# HEX1.net
KiCad netlist of a schematic drawn in Altium Designer
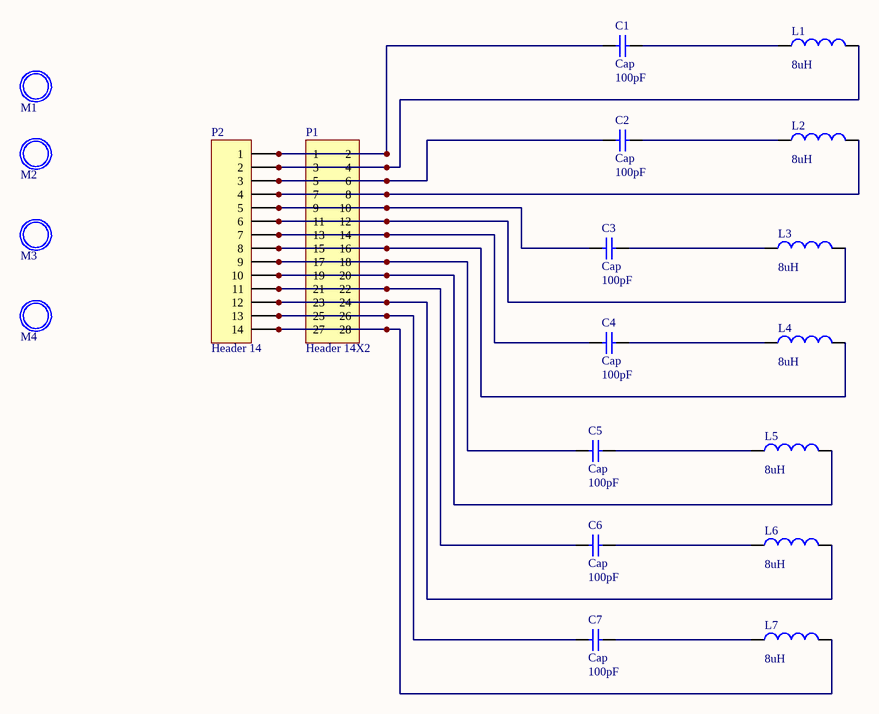
[diagram p0: HEX1.SchDoc]

(export (version "E")
  (design (tool "Eeschema 10.0.6"))
  (components
    (comp (ref "C1")
      (value "Cap")
      (footprint "CAP_MKT")
      (description "Capacitor")
      (fields (field (name "ALTIUM_VALUE") "100pF") (field (name "PUBLISHER") "Altium Limited"))
      (libsource (lib "Miscellaneous Devices") (part "Cap"))
    )
    (comp (ref "C2")
      (value "Cap")
      (footprint "CAP_MKT")
      (description "Capacitor")
      (fields (field (name "ALTIUM_VALUE") "100pF") (field (name "PUBLISHER") "Altium Limited"))
      (libsource (lib "Miscellaneous Devices") (part "Cap"))
    )
    (comp (ref "C3")
      (value "Cap")
      (footprint "CAP_MKT")
      (description "Capacitor")
      (fields (field (name "ALTIUM_VALUE") "100pF") (field (name "PUBLISHER") "Altium Limited"))
      (libsource (lib "Miscellaneous Devices") (part "Cap"))
    )
    (comp (ref "C4")
      (value "Cap")
      (footprint "CAP_MKT")
      (description "Capacitor")
      (fields (field (name "ALTIUM_VALUE") "100pF") (field (name "PUBLISHER") "Altium Limited"))
      (libsource (lib "Miscellaneous Devices") (part "Cap"))
    )
    (comp (ref "C5")
      (value "Cap")
      (footprint "CAP_MKT")
      (description "Capacitor")
      (fields (field (name "ALTIUM_VALUE") "100pF") (field (name "PUBLISHER") "Altium Limited"))
      (libsource (lib "Miscellaneous Devices") (part "Cap"))
    )
    (comp (ref "C6")
      (value "Cap")
      (footprint "CAP_MKT")
      (description "Capacitor")
      (fields (field (name "ALTIUM_VALUE") "100pF") (field (name "PUBLISHER") "Altium Limited"))
      (libsource (lib "Miscellaneous Devices") (part "Cap"))
    )
    (comp (ref "C7")
      (value "Cap")
      (footprint "CAP_MKT")
      (description "Capacitor")
      (fields (field (name "ALTIUM_VALUE") "100pF") (field (name "PUBLISHER") "Altium Limited"))
      (libsource (lib "Miscellaneous Devices") (part "Cap"))
    )
    (comp (ref "L1")
      (value "8uH")
      (footprint "HEXAGON_50-15")
      (description "Inductor")
      (fields (field (name "PUBLISHER") "Altium Limited"))
      (libsource (lib "Miscellaneous Devices") (part "Inductor"))
    )
    (comp (ref "L2")
      (value "8uH")
      (footprint "HEXAGON_50-15")
      (description "Inductor")
      (fields (field (name "PUBLISHER") "Altium Limited"))
      (libsource (lib "Miscellaneous Devices") (part "Inductor"))
    )
    (comp (ref "L3")
      (value "8uH")
      (footprint "HEXAGON_50-15")
      (description "Inductor")
      (fields (field (name "PUBLISHER") "Altium Limited"))
      (libsource (lib "Miscellaneous Devices") (part "Inductor"))
    )
    (comp (ref "L4")
      (value "8uH")
      (footprint "HEXAGON_50-15")
      (description "Inductor")
      (fields (field (name "PUBLISHER") "Altium Limited"))
      (libsource (lib "Miscellaneous Devices") (part "Inductor"))
    )
    (comp (ref "L5")
      (value "8uH")
      (footprint "HEXAGON_50-15")
      (description "Inductor")
      (fields (field (name "PUBLISHER") "Altium Limited"))
      (libsource (lib "Miscellaneous Devices") (part "Inductor"))
    )
    (comp (ref "L6")
      (value "8uH")
      (footprint "HEXAGON_50-15")
      (description "Inductor")
      (fields (field (name "PUBLISHER") "Altium Limited"))
      (libsource (lib "Miscellaneous Devices") (part "Inductor"))
    )
    (comp (ref "L7")
      (value "8uH")
      (footprint "HEXAGON_50-15")
      (description "Inductor")
      (fields (field (name "PUBLISHER") "Altium Limited"))
      (libsource (lib "Miscellaneous Devices") (part "Inductor"))
    )
    (comp (ref "M1")
      (value "Screw")
      (footprint "Board Screw 1")
      (description "Board Screw With Spacer")
      (libsource (lib "Altium") (part "Board Screw"))
    )
    (comp (ref "M2")
      (value "Screw")
      (footprint "Board Screw 1")
      (description "Board Screw With Spacer")
      (libsource (lib "Altium") (part "Board Screw"))
    )
    (comp (ref "M3")
      (value "Screw")
      (footprint "Board Screw 1")
      (description "Board Screw With Spacer")
      (libsource (lib "Altium") (part "Board Screw"))
    )
    (comp (ref "M4")
      (value "Screw")
      (footprint "Board Screw 1")
      (description "Board Screw With Spacer")
      (libsource (lib "Altium") (part "Board Screw"))
    )
    (comp (ref "P1")
      (value "Header 14X2")
      (footprint "HDR2X14")
      (description "Header, 14-Pin, Dual row")
      (fields (field (name "PUBLISHER") "Altium Limited"))
      (libsource (lib "Miscellaneous Connectors") (part "Header 14X2"))
    )
    (comp (ref "P2")
      (value "Header 14")
      (footprint "HDR1X14")
      (description "Header, 14-Pin")
      (fields (field (name "PUBLISHER") "Altium Limited"))
      (libsource (lib "Miscellaneous Connectors") (part "Header 14"))
    )
  )
  (nets
    (net (code "1") (name "Net-(C1-Pad1)") (class "Default")
      (node (ref "C1") (pin "1") (pinfunction "1_1") (pintype "passive"))
      (node (ref "P1") (pin "1") (pinfunction "1_1") (pintype "passive"))
      (node (ref "P1") (pin "2") (pinfunction "2_2") (pintype "passive"))
      (node (ref "P2") (pin "1") (pinfunction "1_1") (pintype "passive"))
    )
    (net (code "2") (name "Net-(C1-Pad2)") (class "Default")
      (node (ref "C1") (pin "2") (pinfunction "2_2") (pintype "passive"))
      (node (ref "L1") (pin "1") (pinfunction "1_1") (pintype "passive"))
    )
    (net (code "3") (name "Net-(C2-Pad1)") (class "Default")
      (node (ref "C2") (pin "1") (pinfunction "1_1") (pintype "passive"))
      (node (ref "P1") (pin "5") (pinfunction "5_5") (pintype "passive"))
      (node (ref "P1") (pin "6") (pinfunction "6_6") (pintype "passive"))
      (node (ref "P2") (pin "3") (pinfunction "3_3") (pintype "passive"))
    )
    (net (code "4") (name "Net-(C2-Pad2)") (class "Default")
      (node (ref "C2") (pin "2") (pinfunction "2_2") (pintype "passive"))
      (node (ref "L2") (pin "1") (pinfunction "1_1") (pintype "passive"))
    )
    (net (code "5") (name "Net-(C3-Pad1)") (class "Default")
      (node (ref "C3") (pin "1") (pinfunction "1_1") (pintype "passive"))
      (node (ref "P1") (pin "10") (pinfunction "10_10") (pintype "passive"))
      (node (ref "P1") (pin "9") (pinfunction "9_9") (pintype "passive"))
      (node (ref "P2") (pin "5") (pinfunction "5_5") (pintype "passive"))
    )
    (net (code "6") (name "Net-(C3-Pad2)") (class "Default")
      (node (ref "C3") (pin "2") (pinfunction "2_2") (pintype "passive"))
      (node (ref "L3") (pin "1") (pinfunction "1_1") (pintype "passive"))
    )
    (net (code "7") (name "Net-(C4-Pad1)") (class "Default")
      (node (ref "C4") (pin "1") (pinfunction "1_1") (pintype "passive"))
      (node (ref "P1") (pin "13") (pinfunction "13_13") (pintype "passive"))
      (node (ref "P1") (pin "14") (pinfunction "14_14") (pintype "passive"))
      (node (ref "P2") (pin "7") (pinfunction "7_7") (pintype "passive"))
    )
    (net (code "8") (name "Net-(C4-Pad2)") (class "Default")
      (node (ref "C4") (pin "2") (pinfunction "2_2") (pintype "passive"))
      (node (ref "L4") (pin "1") (pinfunction "1_1") (pintype "passive"))
    )
    (net (code "9") (name "Net-(C5-Pad1)") (class "Default")
      (node (ref "C5") (pin "1") (pinfunction "1_1") (pintype "passive"))
      (node (ref "P1") (pin "17") (pinfunction "17_17") (pintype "passive"))
      (node (ref "P1") (pin "18") (pinfunction "18_18") (pintype "passive"))
      (node (ref "P2") (pin "9") (pinfunction "9_9") (pintype "passive"))
    )
    (net (code "10") (name "Net-(C5-Pad2)") (class "Default")
      (node (ref "C5") (pin "2") (pinfunction "2_2") (pintype "passive"))
      (node (ref "L5") (pin "1") (pinfunction "1_1") (pintype "passive"))
    )
    (net (code "11") (name "Net-(C6-Pad1)") (class "Default")
      (node (ref "C6") (pin "1") (pinfunction "1_1") (pintype "passive"))
      (node (ref "P1") (pin "21") (pinfunction "21_21") (pintype "passive"))
      (node (ref "P1") (pin "22") (pinfunction "22_22") (pintype "passive"))
      (node (ref "P2") (pin "11") (pinfunction "11_11") (pintype "passive"))
    )
    (net (code "12") (name "Net-(C6-Pad2)") (class "Default")
      (node (ref "C6") (pin "2") (pinfunction "2_2") (pintype "passive"))
      (node (ref "L6") (pin "1") (pinfunction "1_1") (pintype "passive"))
    )
    (net (code "13") (name "Net-(C7-Pad1)") (class "Default")
      (node (ref "C7") (pin "1") (pinfunction "1_1") (pintype "passive"))
      (node (ref "P1") (pin "25") (pinfunction "25_25") (pintype "passive"))
      (node (ref "P1") (pin "26") (pinfunction "26_26") (pintype "passive"))
      (node (ref "P2") (pin "13") (pinfunction "13_13") (pintype "passive"))
    )
    (net (code "14") (name "Net-(C7-Pad2)") (class "Default")
      (node (ref "C7") (pin "2") (pinfunction "2_2") (pintype "passive"))
      (node (ref "L7") (pin "1") (pinfunction "1_1") (pintype "passive"))
    )
    (net (code "15") (name "Net-(L1-Pad2)") (class "Default")
      (node (ref "L1") (pin "2") (pinfunction "2_2") (pintype "passive"))
      (node (ref "P1") (pin "3") (pinfunction "3_3") (pintype "passive"))
      (node (ref "P1") (pin "4") (pinfunction "4_4") (pintype "passive"))
      (node (ref "P2") (pin "2") (pinfunction "2_2") (pintype "passive"))
    )
    (net (code "16") (name "Net-(L2-Pad2)") (class "Default")
      (node (ref "L2") (pin "2") (pinfunction "2_2") (pintype "passive"))
      (node (ref "P1") (pin "7") (pinfunction "7_7") (pintype "passive"))
      (node (ref "P1") (pin "8") (pinfunction "8_8") (pintype "passive"))
      (node (ref "P2") (pin "4") (pinfunction "4_4") (pintype "passive"))
    )
    (net (code "17") (name "Net-(L3-Pad2)") (class "Default")
      (node (ref "L3") (pin "2") (pinfunction "2_2") (pintype "passive"))
      (node (ref "P1") (pin "11") (pinfunction "11_11") (pintype "passive"))
      (node (ref "P1") (pin "12") (pinfunction "12_12") (pintype "passive"))
      (node (ref "P2") (pin "6") (pinfunction "6_6") (pintype "passive"))
    )
    (net (code "18") (name "Net-(L4-Pad2)") (class "Default")
      (node (ref "L4") (pin "2") (pinfunction "2_2") (pintype "passive"))
      (node (ref "P1") (pin "15") (pinfunction "15_15") (pintype "passive"))
      (node (ref "P1") (pin "16") (pinfunction "16_16") (pintype "passive"))
      (node (ref "P2") (pin "8") (pinfunction "8_8") (pintype "passive"))
    )
    (net (code "19") (name "Net-(L5-Pad2)") (class "Default")
      (node (ref "L5") (pin "2") (pinfunction "2_2") (pintype "passive"))
      (node (ref "P1") (pin "19") (pinfunction "19_19") (pintype "passive"))
      (node (ref "P1") (pin "20") (pinfunction "20_20") (pintype "passive"))
      (node (ref "P2") (pin "10") (pinfunction "10_10") (pintype "passive"))
    )
    (net (code "20") (name "Net-(L6-Pad2)") (class "Default")
      (node (ref "L6") (pin "2") (pinfunction "2_2") (pintype "passive"))
      (node (ref "P1") (pin "23") (pinfunction "23_23") (pintype "passive"))
      (node (ref "P1") (pin "24") (pinfunction "24_24") (pintype "passive"))
      (node (ref "P2") (pin "12") (pinfunction "12_12") (pintype "passive"))
    )
    (net (code "21") (name "Net-(L7-Pad2)") (class "Default")
      (node (ref "L7") (pin "2") (pinfunction "2_2") (pintype "passive"))
      (node (ref "P1") (pin "27") (pinfunction "27_27") (pintype "passive"))
      (node (ref "P1") (pin "28") (pinfunction "28_28") (pintype "passive"))
      (node (ref "P2") (pin "14") (pinfunction "14_14") (pintype "passive"))
    )
  )
)
